# oneDpong.net
KiCad netlist of a schematic drawn in EAGLE
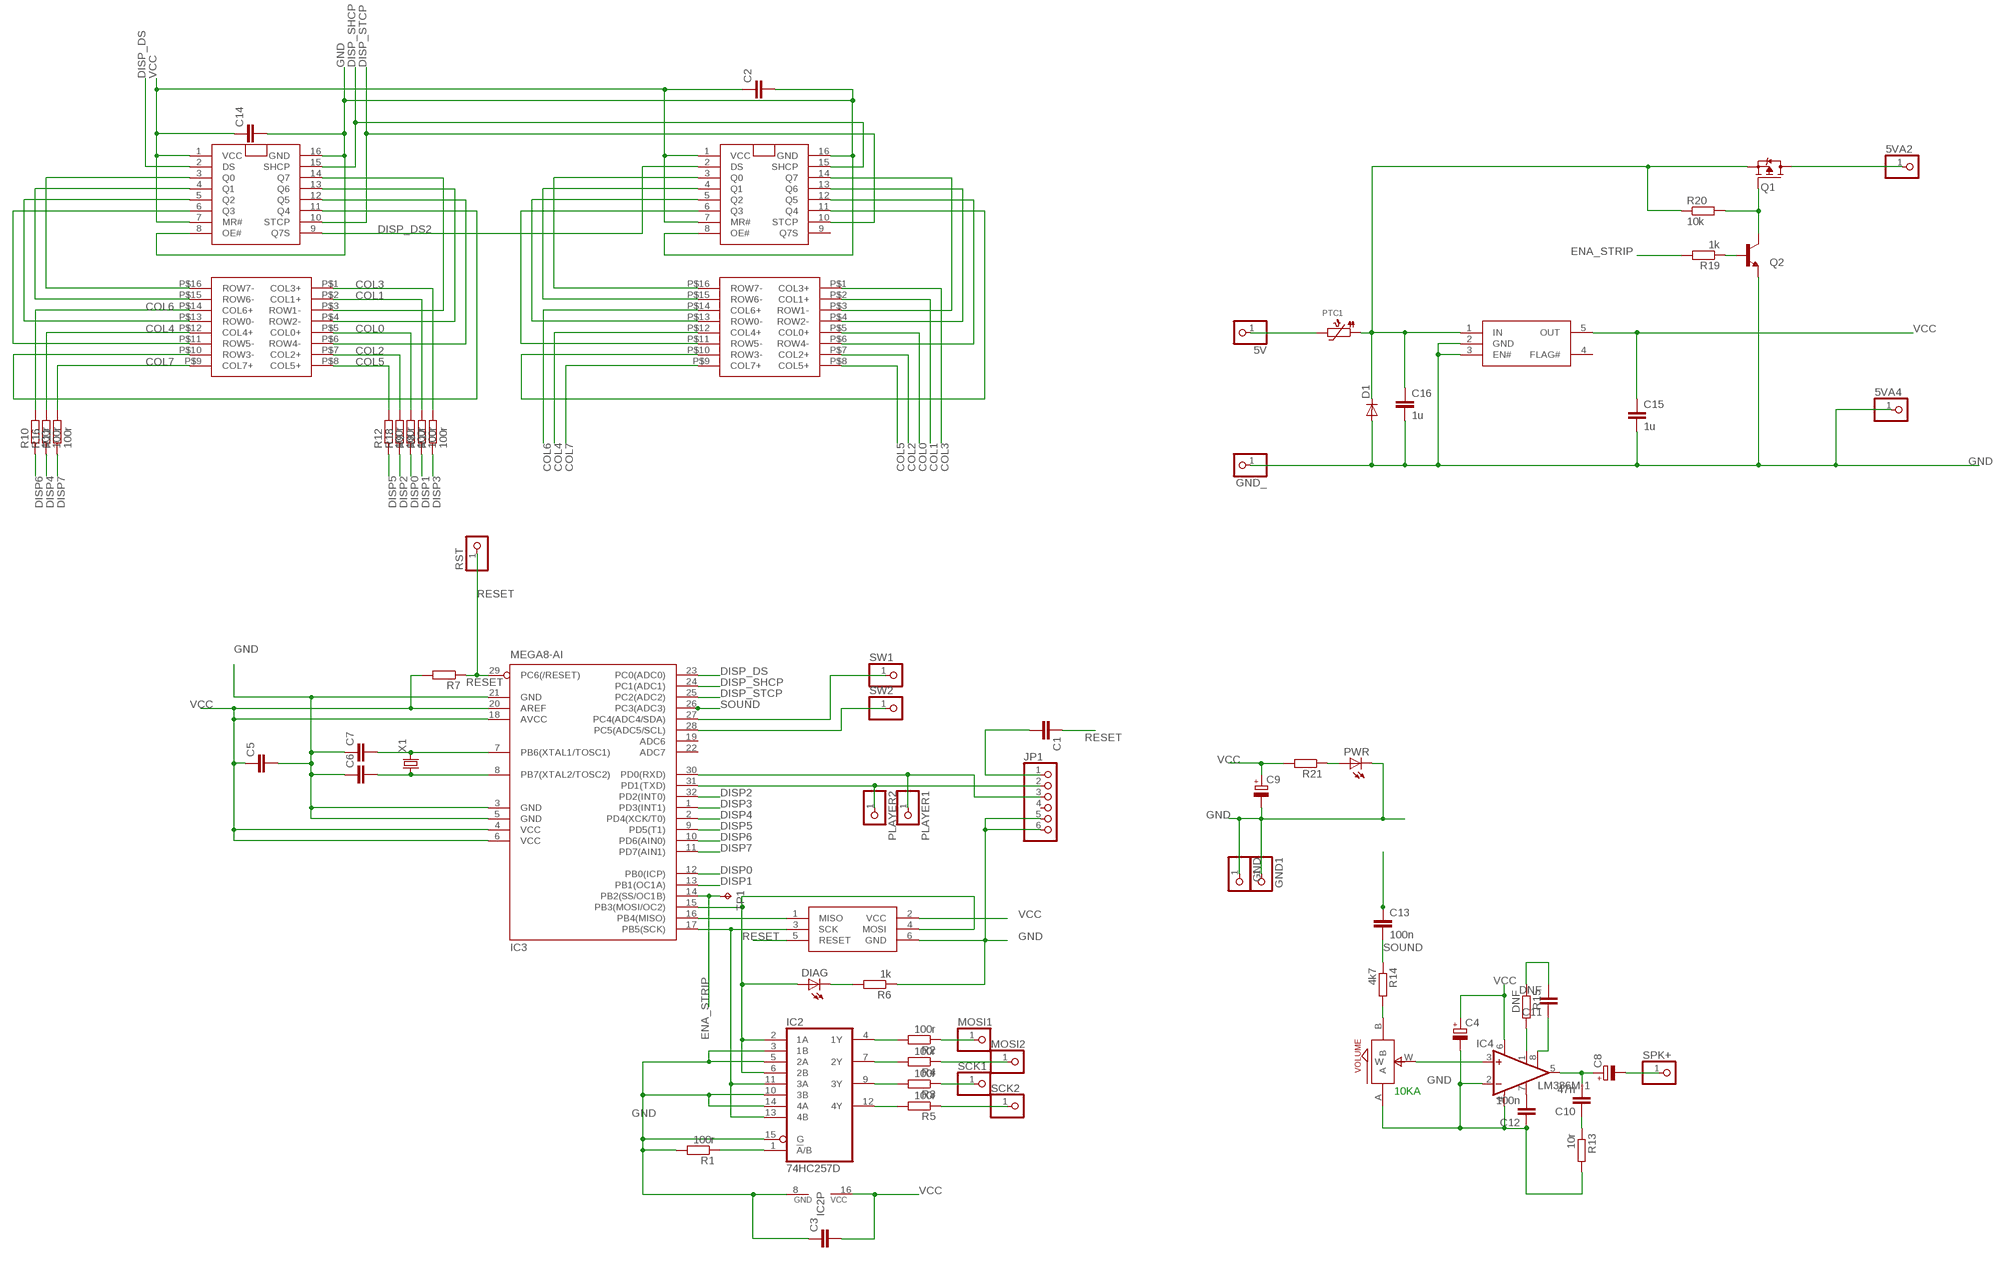
[diagram p0: schematic, sheet 1]

(export (version "E")
  (design (tool "Eeschema 10.0.6"))
  (components
    (comp (ref "5V")
      (value "PINHD-1X1")
      (footprint "eagle-import:1X01")
      (libsource (lib "eagle-import") (part "PINHD-1X1"))
    )
    (comp (ref "5VA2")
      (value "PINHD-1X1")
      (footprint "eagle-import:1X01")
      (libsource (lib "eagle-import") (part "PINHD-1X1"))
    )
    (comp (ref "5VA4")
      (value "PINHD-1X1")
      (footprint "eagle-import:1X01")
      (libsource (lib "eagle-import") (part "PINHD-1X1"))
    )
    (comp (ref "C1")
      (value "C-EUC0805")
      (footprint "eagle-import:C0805")
      (libsource (lib "eagle-import") (part "C-EUC0805"))
    )
    (comp (ref "C2")
      (value "C-EUC0805")
      (footprint "eagle-import:C0805")
      (libsource (lib "eagle-import") (part "C-EUC0805"))
    )
    (comp (ref "C3")
      (value "C-EUC0805")
      (footprint "eagle-import:C0805")
      (libsource (lib "eagle-import") (part "C-EUC0805"))
    )
    (comp (ref "C4")
      (value "CPOL-EUE2.5-6")
      (footprint "eagle-import:E2,5-6")
      (libsource (lib "eagle-import") (part "CPOL-EUE2.5-6"))
    )
    (comp (ref "C5")
      (value "C-EUC0805")
      (footprint "eagle-import:C0805")
      (libsource (lib "eagle-import") (part "C-EUC0805"))
    )
    (comp (ref "C6")
      (value "C-EUC0805")
      (footprint "eagle-import:C0805")
      (libsource (lib "eagle-import") (part "C-EUC0805"))
    )
    (comp (ref "C7")
      (value "C-EUC0805")
      (footprint "eagle-import:C0805")
      (libsource (lib "eagle-import") (part "C-EUC0805"))
    )
    (comp (ref "C8")
      (value "CPOL-EUE2.5-6")
      (footprint "eagle-import:E2,5-6")
      (libsource (lib "eagle-import") (part "CPOL-EUE2.5-6"))
    )
    (comp (ref "C9")
      (value "CPOL-EUE2.5-6")
      (footprint "eagle-import:E2,5-6")
      (libsource (lib "eagle-import") (part "CPOL-EUE2.5-6"))
    )
    (comp (ref "C10")
      (value "47n")
      (footprint "eagle-import:C0805")
      (libsource (lib "eagle-import") (part "C-EUC0805"))
    )
    (comp (ref "C11")
      (value "DNF")
      (footprint "eagle-import:C0805")
      (libsource (lib "eagle-import") (part "C-EUC0805"))
    )
    (comp (ref "C12")
      (value "100n")
      (footprint "eagle-import:C0805")
      (libsource (lib "eagle-import") (part "C-EUC0805"))
    )
    (comp (ref "C13")
      (value "100n")
      (footprint "eagle-import:C0805")
      (libsource (lib "eagle-import") (part "C-EUC0805"))
    )
    (comp (ref "C14")
      (value "C-EUC0805")
      (footprint "eagle-import:C0805")
      (libsource (lib "eagle-import") (part "C-EUC0805"))
    )
    (comp (ref "C15")
      (value "1u")
      (footprint "eagle-import:C0805")
      (libsource (lib "eagle-import") (part "C-EUC0805"))
    )
    (comp (ref "C16")
      (value "1u")
      (footprint "eagle-import:C0805")
      (libsource (lib "eagle-import") (part "C-EUC0805"))
    )
    (comp (ref "D1")
      (value "DIODE-SMC")
      (footprint "eagle-import:SMC")
      (libsource (lib "eagle-import") (part "DIODE-SMC"))
    )
    (comp (ref "DIAG")
      (value "LED3MM")
      (footprint "eagle-import:LED3MM")
      (libsource (lib "eagle-import") (part "LED3MM"))
    )
    (comp (ref "GND")
      (value "PINHD-1X1")
      (footprint "eagle-import:1X01")
      (libsource (lib "eagle-import") (part "PINHD-1X1"))
    )
    (comp (ref "GND1")
      (value "PINHD-1X1")
      (footprint "eagle-import:1X01")
      (libsource (lib "eagle-import") (part "PINHD-1X1"))
    )
    (comp (ref "GND_")
      (value "PINHD-1X1")
      (footprint "eagle-import:1X01")
      (libsource (lib "eagle-import") (part "PINHD-1X1"))
    )
    (comp (ref "IC1")
      (value "NPIC6C596")
      (footprint "eagle-import:SO16")
      (libsource (lib "eagle-import") (part "NPIC6C596"))
    )
    (comp (ref "IC2")
      (value "74HC257D")
      (footprint "eagle-import:SO16")
      (libsource (lib "eagle-import") (part "74257DHC"))
    )
    (comp (ref "IC3")
      (value "MEGA8-AI")
      (footprint "eagle-import:TQFP32-08")
      (fields (field (name "MPN") "ATMEGA8-16AU"))
      (libsource (lib "eagle-import") (part "MEGA8-AI"))
    )
    (comp (ref "IC4")
      (value "LM386M-1")
      (footprint "eagle-import:SO08")
      (libsource (lib "eagle-import") (part "LM386?-M1"))
    )
    (comp (ref "IC5")
      (value "NPIC6C596")
      (footprint "eagle-import:SO16")
      (libsource (lib "eagle-import") (part "NPIC6C596"))
    )
    (comp (ref "IC6")
      (value "NCP361SNT1G")
      (footprint "eagle-import:SOT23-5")
      (libsource (lib "eagle-import") (part "NCP361SNT1G"))
    )
    (comp (ref "ICSP")
      (value "TAG_CONN_AVR")
      (footprint "eagle-import:TC2030-MCP-NL")
      (libsource (lib "eagle-import") (part "TAG_CONN_AVR"))
    )
    (comp (ref "JP1")
      (value "PINHD-1X6")
      (footprint "eagle-import:1X06")
      (libsource (lib "eagle-import") (part "PINHD-1X6"))
    )
    (comp (ref "MOSI1")
      (value "PINHD-1X1")
      (footprint "eagle-import:1X01")
      (libsource (lib "eagle-import") (part "PINHD-1X1"))
    )
    (comp (ref "MOSI2")
      (value "PINHD-1X1")
      (footprint "eagle-import:1X01")
      (libsource (lib "eagle-import") (part "PINHD-1X1"))
    )
    (comp (ref "PLAYER1")
      (value "PINHD-1X1")
      (footprint "eagle-import:1X01")
      (libsource (lib "eagle-import") (part "PINHD-1X1"))
    )
    (comp (ref "PLAYER2")
      (value "PINHD-1X1")
      (footprint "eagle-import:1X01")
      (libsource (lib "eagle-import") (part "PINHD-1X1"))
    )
    (comp (ref "PTC1")
      (value "PTC1812")
      (footprint "eagle-import:PTC1812")
      (libsource (lib "eagle-import") (part "PTC1812"))
    )
    (comp (ref "PWR")
      (value "LED3MM")
      (footprint "eagle-import:LED3MM")
      (libsource (lib "eagle-import") (part "LED3MM"))
    )
    (comp (ref "Q1")
      (value "SPD30P06PTO252")
      (footprint "eagle-import:TO252")
      (libsource (lib "eagle-import") (part "SPD30P06PTO252"))
    )
    (comp (ref "Q2")
      (value "MMBT3904LT1-NPN-SOT23-BEC")
      (footprint "eagle-import:SOT23-BEC")
      (libsource (lib "eagle-import") (part "-NPN-SOT23-BECMMBT3904LT1"))
    )
    (comp (ref "R1")
      (value "100r")
      (footprint "eagle-import:R0805")
      (libsource (lib "eagle-import") (part "R-EU_R0805"))
    )
    (comp (ref "R2")
      (value "100r")
      (footprint "eagle-import:R0805")
      (libsource (lib "eagle-import") (part "R-EU_R0805"))
    )
    (comp (ref "R3")
      (value "100r")
      (footprint "eagle-import:R0805")
      (libsource (lib "eagle-import") (part "R-EU_R0805"))
    )
    (comp (ref "R4")
      (value "100r")
      (footprint "eagle-import:R0805")
      (libsource (lib "eagle-import") (part "R-EU_R0805"))
    )
    (comp (ref "R5")
      (value "100r")
      (footprint "eagle-import:R0805")
      (libsource (lib "eagle-import") (part "R-EU_R0805"))
    )
    (comp (ref "R6")
      (value "1k")
      (footprint "eagle-import:R0805")
      (libsource (lib "eagle-import") (part "R-EU_R0805"))
    )
    (comp (ref "R7")
      (value "R-EU_R0805")
      (footprint "eagle-import:R0805")
      (libsource (lib "eagle-import") (part "R-EU_R0805"))
    )
    (comp (ref "R8")
      (value "100r")
      (footprint "eagle-import:R0805")
      (libsource (lib "eagle-import") (part "R-EU_R0805"))
    )
    (comp (ref "R9")
      (value "100r")
      (footprint "eagle-import:R0805")
      (libsource (lib "eagle-import") (part "R-EU_R0805"))
    )
    (comp (ref "R10")
      (value "100r")
      (footprint "eagle-import:R0805")
      (libsource (lib "eagle-import") (part "R-EU_R0805"))
    )
    (comp (ref "R11")
      (value "100r")
      (footprint "eagle-import:R0805")
      (libsource (lib "eagle-import") (part "R-EU_R0805"))
    )
    (comp (ref "R12")
      (value "100r")
      (footprint "eagle-import:R0805")
      (libsource (lib "eagle-import") (part "R-EU_R0805"))
    )
    (comp (ref "R13")
      (value "10r")
      (footprint "eagle-import:R0805")
      (libsource (lib "eagle-import") (part "R-EU_R0805"))
    )
    (comp (ref "R14")
      (value "4k7")
      (footprint "eagle-import:R0805")
      (libsource (lib "eagle-import") (part "R-EU_R0805"))
    )
    (comp (ref "R15")
      (value "DNF")
      (footprint "eagle-import:R0805")
      (libsource (lib "eagle-import") (part "R-EU_R0805"))
    )
    (comp (ref "R16")
      (value "100r")
      (footprint "eagle-import:R0805")
      (libsource (lib "eagle-import") (part "R-EU_R0805"))
    )
    (comp (ref "R17")
      (value "100r")
      (footprint "eagle-import:R0805")
      (libsource (lib "eagle-import") (part "R-EU_R0805"))
    )
    (comp (ref "R18")
      (value "100r")
      (footprint "eagle-import:R0805")
      (libsource (lib "eagle-import") (part "R-EU_R0805"))
    )
    (comp (ref "R19")
      (value "1k")
      (footprint "eagle-import:R0805")
      (libsource (lib "eagle-import") (part "R-EU_R0805"))
    )
    (comp (ref "R20")
      (value "10k")
      (footprint "eagle-import:R0805")
      (libsource (lib "eagle-import") (part "R-EU_R0805"))
    )
    (comp (ref "R21")
      (value "R-EU_R0805")
      (footprint "eagle-import:R0805")
      (libsource (lib "eagle-import") (part "R-EU_R0805"))
    )
    (comp (ref "RST")
      (value "PINHD-1X1")
      (footprint "eagle-import:1X01")
      (libsource (lib "eagle-import") (part "PINHD-1X1"))
    )
    (comp (ref "SCK1")
      (value "PINHD-1X1")
      (footprint "eagle-import:1X01")
      (libsource (lib "eagle-import") (part "PINHD-1X1"))
    )
    (comp (ref "SCK2")
      (value "PINHD-1X1")
      (footprint "eagle-import:1X01")
      (libsource (lib "eagle-import") (part "PINHD-1X1"))
    )
    (comp (ref "SPK+")
      (value "PINHD-1X1")
      (footprint "eagle-import:1X01")
      (libsource (lib "eagle-import") (part "PINHD-1X1"))
    )
    (comp (ref "SW1")
      (value "PINHD-1X1")
      (footprint "eagle-import:1X01")
      (libsource (lib "eagle-import") (part "PINHD-1X1"))
    )
    (comp (ref "SW2")
      (value "PINHD-1X1")
      (footprint "eagle-import:1X01")
      (libsource (lib "eagle-import") (part "PINHD-1X1"))
    )
    (comp (ref "TP1")
      (value "TPB1,27")
      (footprint "eagle-import:B1,27")
      (libsource (lib "eagle-import") (part "TPB1,27"))
    )
    (comp (ref "U$1")
      (value "LARGE8X8")
      (footprint "eagle-import:LARGE8X8")
      (libsource (lib "eagle-import") (part "LARGE8X8"))
    )
    (comp (ref "U$2")
      (value "LARGE8X8")
      (footprint "eagle-import:LARGE8X8")
      (libsource (lib "eagle-import") (part "LARGE8X8"))
    )
    (comp (ref "VOLUME")
      (value "ALPS_POT_SMALL")
      (footprint "eagle-import:SMALL_ALPS_POT")
      (libsource (lib "eagle-import") (part "ALPS_POT_SMALL"))
    )
    (comp (ref "X1")
      (value "CRYSTALHC49U-V")
      (footprint "eagle-import:HC49U-V")
      (libsource (lib "eagle-import") (part "CRYSTALHC49U-V"))
    )
  )
  (nets
    (net (code "1") (name "/COL0") (class "Default")
      (node (ref "R9") (pin "2") (pinfunction "2_2") (pintype "passive"))
      (node (ref "U$1") (pin "P$5") (pinfunction "COL0+_P$5") (pintype "bidirectional"))
      (node (ref "U$2") (pin "P$5") (pinfunction "COL0+_P$5") (pintype "bidirectional"))
    )
    (net (code "2") (name "/COL1") (class "Default")
      (node (ref "R8") (pin "2") (pinfunction "2_2") (pintype "passive"))
      (node (ref "U$1") (pin "P$2") (pinfunction "COL1+_P$2") (pintype "bidirectional"))
      (node (ref "U$2") (pin "P$2") (pinfunction "COL1+_P$2") (pintype "bidirectional"))
    )
    (net (code "3") (name "/COL2") (class "Default")
      (node (ref "R18") (pin "2") (pinfunction "2_2") (pintype "passive"))
      (node (ref "U$1") (pin "P$7") (pinfunction "COL2+_P$7") (pintype "bidirectional"))
      (node (ref "U$2") (pin "P$7") (pinfunction "COL2+_P$7") (pintype "bidirectional"))
    )
    (net (code "4") (name "/COL3") (class "Default")
      (node (ref "R17") (pin "2") (pinfunction "2_2") (pintype "passive"))
      (node (ref "U$1") (pin "P$1") (pinfunction "COL3+_P$1") (pintype "bidirectional"))
      (node (ref "U$2") (pin "P$1") (pinfunction "COL3+_P$1") (pintype "bidirectional"))
    )
    (net (code "5") (name "/COL4") (class "Default")
      (node (ref "R16") (pin "2") (pinfunction "2_2") (pintype "passive"))
      (node (ref "U$1") (pin "P$12") (pinfunction "COL4+_P$12") (pintype "bidirectional"))
      (node (ref "U$2") (pin "P$12") (pinfunction "COL4+_P$12") (pintype "bidirectional"))
    )
    (net (code "6") (name "/COL5") (class "Default")
      (node (ref "R12") (pin "2") (pinfunction "2_2") (pintype "passive"))
      (node (ref "U$1") (pin "P$8") (pinfunction "COL5+_P$8") (pintype "bidirectional"))
      (node (ref "U$2") (pin "P$8") (pinfunction "COL5+_P$8") (pintype "bidirectional"))
    )
    (net (code "7") (name "/COL6") (class "Default")
      (node (ref "R10") (pin "2") (pinfunction "2_2") (pintype "passive"))
      (node (ref "U$1") (pin "P$14") (pinfunction "COL6+_P$14") (pintype "bidirectional"))
      (node (ref "U$2") (pin "P$14") (pinfunction "COL6+_P$14") (pintype "bidirectional"))
    )
    (net (code "8") (name "/COL7") (class "Default")
      (node (ref "R11") (pin "2") (pinfunction "2_2") (pintype "passive"))
      (node (ref "U$1") (pin "P$9") (pinfunction "COL7+_P$9") (pintype "bidirectional"))
      (node (ref "U$2") (pin "P$9") (pinfunction "COL7+_P$9") (pintype "bidirectional"))
    )
    (net (code "9") (name "/DISP0") (class "Default")
      (node (ref "IC3") (pin "12") (pinfunction "PB0(ICP)_12") (pintype "bidirectional"))
      (node (ref "R9") (pin "1") (pinfunction "1_1") (pintype "passive"))
    )
    (net (code "10") (name "/DISP1") (class "Default")
      (node (ref "IC3") (pin "13") (pinfunction "PB1(OC1A)_13") (pintype "bidirectional"))
      (node (ref "R8") (pin "1") (pinfunction "1_1") (pintype "passive"))
    )
    (net (code "11") (name "/DISP2") (class "Default")
      (node (ref "IC3") (pin "32") (pinfunction "PD2(INT0)_32") (pintype "bidirectional"))
      (node (ref "R18") (pin "1") (pinfunction "1_1") (pintype "passive"))
    )
    (net (code "12") (name "/DISP3") (class "Default")
      (node (ref "IC3") (pin "1") (pinfunction "PD3(INT1)_1") (pintype "bidirectional"))
      (node (ref "R17") (pin "1") (pinfunction "1_1") (pintype "passive"))
    )
    (net (code "13") (name "/DISP4") (class "Default")
      (node (ref "IC3") (pin "2") (pinfunction "PD4(XCK/T0)_2") (pintype "bidirectional"))
      (node (ref "R16") (pin "1") (pinfunction "1_1") (pintype "passive"))
    )
    (net (code "14") (name "/DISP5") (class "Default")
      (node (ref "IC3") (pin "9") (pinfunction "PD5(T1)_9") (pintype "bidirectional"))
      (node (ref "R12") (pin "1") (pinfunction "1_1") (pintype "passive"))
    )
    (net (code "15") (name "/DISP6") (class "Default")
      (node (ref "IC3") (pin "10") (pinfunction "PD6(AIN0)_10") (pintype "bidirectional"))
      (node (ref "R10") (pin "1") (pinfunction "1_1") (pintype "passive"))
    )
    (net (code "16") (name "/DISP7") (class "Default")
      (node (ref "IC3") (pin "11") (pinfunction "PD7(AIN1)_11") (pintype "bidirectional"))
      (node (ref "R11") (pin "1") (pinfunction "1_1") (pintype "passive"))
    )
    (net (code "17") (name "/DISP_DS") (class "Default")
      (node (ref "IC3") (pin "23") (pinfunction "PC0(ADC0)_23") (pintype "bidirectional"))
      (node (ref "IC5") (pin "2") (pinfunction "DS_2") (pintype "input"))
    )
    (net (code "18") (name "/DISP_DS2") (class "Default")
      (node (ref "IC1") (pin "2") (pinfunction "DS_2") (pintype "input"))
      (node (ref "IC5") (pin "9") (pinfunction "Q7S_9") (pintype "output"))
    )
    (net (code "19") (name "/DISP_SHCP") (class "Default")
      (node (ref "IC1") (pin "15") (pinfunction "SHCP_15") (pintype "input"))
      (node (ref "IC3") (pin "24") (pinfunction "PC1(ADC1)_24") (pintype "bidirectional"))
      (node (ref "IC5") (pin "15") (pinfunction "SHCP_15") (pintype "input"))
    )
    (net (code "20") (name "/DISP_STCP") (class "Default")
      (node (ref "IC1") (pin "10") (pinfunction "STCP_10") (pintype "input"))
      (node (ref "IC3") (pin "25") (pinfunction "PC2(ADC2)_25") (pintype "bidirectional"))
      (node (ref "IC5") (pin "10") (pinfunction "STCP_10") (pintype "input"))
    )
    (net (code "21") (name "/ENA_STRIP") (class "Default")
      (node (ref "IC3") (pin "14") (pinfunction "PB2(SS/OC1B)_14") (pintype "bidirectional"))
      (node (ref "R19") (pin "2") (pinfunction "2_2") (pintype "passive"))
      (node (ref "TP1") (pin "TP") (pinfunction "TP_TP") (pintype "input"))
    )
    (net (code "22") (name "/GND") (class "Default")
      (node (ref "5VA4") (pin "1") (pinfunction "1_1") (pintype "passive"))
      (node (ref "C12") (pin "1") (pinfunction "1_1") (pintype "passive"))
      (node (ref "C14") (pin "2") (pinfunction "2_2") (pintype "passive"))
      (node (ref "C15") (pin "2") (pinfunction "2_2") (pintype "passive"))
      (node (ref "C16") (pin "2") (pinfunction "2_2") (pintype "passive"))
      (node (ref "C2") (pin "2") (pinfunction "2_2") (pintype "passive"))
      (node (ref "C3") (pin "1") (pinfunction "1_1") (pintype "passive"))
      (node (ref "C4") (pin "-") (pinfunction "-_-") (pintype "passive"))
      (node (ref "C5") (pin "2") (pinfunction "2_2") (pintype "passive"))
      (node (ref "C6") (pin "1") (pinfunction "1_1") (pintype "passive"))
      (node (ref "C7") (pin "1") (pinfunction "1_1") (pintype "passive"))
      (node (ref "C9") (pin "-") (pinfunction "-_-") (pintype "passive"))
      (node (ref "D1") (pin "A") (pinfunction "A_A") (pintype "passive"))
      (node (ref "GND") (pin "1") (pinfunction "1_1") (pintype "passive"))
      (node (ref "GND1") (pin "1") (pinfunction "1_1") (pintype "passive"))
      (node (ref "GND_") (pin "1") (pinfunction "1_1") (pintype "passive"))
      (node (ref "IC1") (pin "16") (pinfunction "GND_16") (pintype "power_in"))
      (node (ref "IC1") (pin "8") (pinfunction "OE#_8") (pintype "input"))
      (node (ref "IC2") (pin "10") (pinfunction "3B_10") (pintype "input"))
      (node (ref "IC2") (pin "14") (pinfunction "4A_14") (pintype "input"))
      (node (ref "IC2") (pin "15") (pinfunction "G_15") (pintype "input"))
      (node (ref "IC2") (pin "3") (pinfunction "1B_3") (pintype "input"))
      (node (ref "IC2") (pin "5") (pinfunction "2A_5") (pintype "input"))
      (node (ref "IC2") (pin "8") (pinfunction "GND_8") (pintype "power_in"))
      (node (ref "IC3") (pin "21") (pinfunction "GND_21") (pintype "power_in"))
      (node (ref "IC3") (pin "3") (pinfunction "GND_3") (pintype "power_in"))
      (node (ref "IC3") (pin "5") (pinfunction "GND_5") (pintype "power_in"))
      (node (ref "IC4") (pin "2") (pinfunction "-IN_2") (pintype "input"))
      (node (ref "IC4") (pin "4") (pinfunction "GND_4") (pintype "power_in"))
      (node (ref "IC5") (pin "16") (pinfunction "GND_16") (pintype "power_in"))
      (node (ref "IC5") (pin "8") (pinfunction "OE#_8") (pintype "input"))
      (node (ref "IC6") (pin "2") (pinfunction "GND_2") (pintype "bidirectional"))
      (node (ref "IC6") (pin "3") (pinfunction "EN#_3") (pintype "bidirectional"))
      (node (ref "ICSP") (pin "6") (pinfunction "GND_6") (pintype "power_in"))
      (node (ref "JP1") (pin "5") (pinfunction "5_5") (pintype "passive"))
      (node (ref "JP1") (pin "6") (pinfunction "6_6") (pintype "passive"))
      (node (ref "PWR") (pin "K") (pinfunction "C_K") (pintype "passive"))
      (node (ref "Q2") (pin "E") (pinfunction "E_E") (pintype "passive"))
      (node (ref "R1") (pin "2") (pinfunction "2_2") (pintype "passive"))
      (node (ref "R13") (pin "2") (pinfunction "2_2") (pintype "passive"))
      (node (ref "R6") (pin "1") (pinfunction "1_1") (pintype "passive"))
      (node (ref "VOLUME") (pin "A") (pinfunction "A_A") (pintype "bidirectional"))
    )
    (net (code "23") (name "/RESET") (class "Default")
      (node (ref "C1") (pin "1") (pinfunction "1_1") (pintype "passive"))
      (node (ref "IC3") (pin "29") (pinfunction "PC6(/RESET)_29") (pintype "bidirectional"))
      (node (ref "ICSP") (pin "5") (pinfunction "RESET_5") (pintype "bidirectional"))
      (node (ref "R7") (pin "1") (pinfunction "1_1") (pintype "passive"))
      (node (ref "RST") (pin "1") (pinfunction "1_1") (pintype "passive"))
    )
    (net (code "24") (name "/SOUND") (class "Default")
      (node (ref "C13") (pin "1") (pinfunction "1_1") (pintype "passive"))
      (node (ref "IC3") (pin "26") (pinfunction "PC3(ADC3)_26") (pintype "bidirectional"))
    )
    (net (code "25") (name "/VCC") (class "Default")
      (node (ref "C14") (pin "1") (pinfunction "1_1") (pintype "passive"))
      (node (ref "C15") (pin "1") (pinfunction "1_1") (pintype "passive"))
      (node (ref "C2") (pin "1") (pinfunction "1_1") (pintype "passive"))
      (node (ref "C3") (pin "2") (pinfunction "2_2") (pintype "passive"))
      (node (ref "C4") (pin "+") (pinfunction "+_+") (pintype "passive"))
      (node (ref "C5") (pin "1") (pinfunction "1_1") (pintype "passive"))
      (node (ref "C9") (pin "+") (pinfunction "+_+") (pintype "passive"))
      (node (ref "IC1") (pin "1") (pinfunction "VCC_1") (pintype "power_in"))
      (node (ref "IC1") (pin "7") (pinfunction "MR#_7") (pintype "input"))
      (node (ref "IC2") (pin "16") (pinfunction "VCC_16") (pintype "power_in"))
      (node (ref "IC3") (pin "18") (pinfunction "AVCC_18") (pintype "power_in"))
      (node (ref "IC3") (pin "20") (pinfunction "AREF_20") (pintype "passive"))
      (node (ref "IC3") (pin "4") (pinfunction "VCC_4") (pintype "power_in"))
      (node (ref "IC3") (pin "6") (pinfunction "VCC_6") (pintype "power_in"))
      (node (ref "IC4") (pin "6") (pinfunction "VS_6") (pintype "power_in"))
      (node (ref "IC5") (pin "1") (pinfunction "VCC_1") (pintype "power_in"))
      (node (ref "IC5") (pin "7") (pinfunction "MR#_7") (pintype "input"))
      (node (ref "IC6") (pin "5") (pinfunction "OUT_5") (pintype "bidirectional"))
      (node (ref "ICSP") (pin "2") (pinfunction "VCC_2") (pintype "power_in"))
      (node (ref "R21") (pin "2") (pinfunction "2_2") (pintype "passive"))
      (node (ref "R7") (pin "2") (pinfunction "2_2") (pintype "passive"))
    )
    (net (code "26") (name "Net-(C1-Pad2)") (class "Default")
      (node (ref "C1") (pin "2") (pinfunction "2_2") (pintype "passive"))
      (node (ref "JP1") (pin "1") (pinfunction "1_1") (pintype "passive"))
    )
    (net (code "27") (name "Net-(C8-Pad-)") (class "Default")
      (node (ref "C8") (pin "-") (pinfunction "-_-") (pintype "passive"))
      (node (ref "SPK+") (pin "1") (pinfunction "1_1") (pintype "passive"))
    )
    (net (code "28") (name "Net-(C10-Pad1)") (class "Default")
      (node (ref "C10") (pin "1") (pinfunction "1_1") (pintype "passive"))
      (node (ref "R13") (pin "1") (pinfunction "1_1") (pintype "passive"))
    )
    (net (code "29") (name "Net-(C11-Pad1)") (class "Default")
      (node (ref "C11") (pin "1") (pinfunction "1_1") (pintype "passive"))
      (node (ref "IC4") (pin "8") (pinfunction "GAIN_8") (pintype "passive"))
    )
    (net (code "30") (name "Net-(C11-Pad2)") (class "Default")
      (node (ref "C11") (pin "2") (pinfunction "2_2") (pintype "passive"))
      (node (ref "R15") (pin "1") (pinfunction "1_1") (pintype "passive"))
    )
    (net (code "31") (name "Net-(C13-Pad2)") (class "Default")
      (node (ref "C13") (pin "2") (pinfunction "2_2") (pintype "passive"))
      (node (ref "R14") (pin "1") (pinfunction "1_1") (pintype "passive"))
    )
    (net (code "32") (name "Net-(DIAG-C)") (class "Default")
      (node (ref "DIAG") (pin "K") (pinfunction "C_K") (pintype "passive"))
      (node (ref "R6") (pin "2") (pinfunction "2_2") (pintype "passive"))
    )
    (net (code "33") (name "Net-(IC1-Q0)") (class "Default")
      (node (ref "IC1") (pin "3") (pinfunction "Q0_3") (pintype "open_collector"))
      (node (ref "U$2") (pin "P$16") (pinfunction "ROW7-_P$16") (pintype "bidirectional"))
    )
    (net (code "34") (name "Net-(IC1-Q1)") (class "Default")
      (node (ref "IC1") (pin "4") (pinfunction "Q1_4") (pintype "open_collector"))
      (node (ref "U$2") (pin "P$15") (pinfunction "ROW6-_P$15") (pintype "bidirectional"))
    )
    (net (code "35") (name "Net-(IC1-Q2)") (class "Default")
      (node (ref "IC1") (pin "5") (pinfunction "Q2_5") (pintype "open_collector"))
      (node (ref "U$2") (pin "P$13") (pinfunction "ROW0-_P$13") (pintype "bidirectional"))
    )
    (net (code "36") (name "Net-(IC1-Q3)") (class "Default")
      (node (ref "IC1") (pin "6") (pinfunction "Q3_6") (pintype "open_collector"))
      (node (ref "U$2") (pin "P$11") (pinfunction "ROW5-_P$11") (pintype "bidirectional"))
    )
    (net (code "37") (name "Net-(IC1-Q4)") (class "Default")
      (node (ref "IC1") (pin "11") (pinfunction "Q4_11") (pintype "open_collector"))
      (node (ref "U$2") (pin "P$10") (pinfunction "ROW3-_P$10") (pintype "bidirectional"))
    )
    (net (code "38") (name "Net-(IC1-Q5)") (class "Default")
      (node (ref "IC1") (pin "12") (pinfunction "Q5_12") (pintype "open_collector"))
      (node (ref "U$2") (pin "P$6") (pinfunction "ROW4-_P$6") (pintype "bidirectional"))
    )
    (net (code "39") (name "Net-(IC1-Q6)") (class "Default")
      (node (ref "IC1") (pin "13") (pinfunction "Q6_13") (pintype "open_collector"))
      (node (ref "U$2") (pin "P$4") (pinfunction "ROW2-_P$4") (pintype "bidirectional"))
    )
    (net (code "40") (name "Net-(IC1-Q7)") (class "Default")
      (node (ref "IC1") (pin "14") (pinfunction "Q7_14") (pintype "open_collector"))
      (node (ref "U$2") (pin "P$3") (pinfunction "ROW1-_P$3") (pintype "bidirectional"))
    )
    (net (code "41") (name "Net-(IC2A-1A)") (class "Default")
      (node (ref "DIAG") (pin "A") (pinfunction "A_A") (pintype "passive"))
      (node (ref "IC2") (pin "2") (pinfunction "1A_2") (pintype "input"))
      (node (ref "IC2") (pin "6") (pinfunction "2B_6") (pintype "input"))
      (node (ref "IC3") (pin "15") (pinfunction "PB3(MOSI/OC2)_15") (pintype "bidirectional"))
      (node (ref "ICSP") (pin "4") (pinfunction "MOSI_4") (pintype "bidirectional"))
    )
    (net (code "42") (name "Net-(IC2A-1Y)") (class "Default")
      (node (ref "IC2") (pin "4") (pinfunction "1Y_4") (pintype "tri_state"))
      (node (ref "R2") (pin "2") (pinfunction "2_2") (pintype "passive"))
    )
    (net (code "43") (name "Net-(IC2A-2Y)") (class "Default")
      (node (ref "IC2") (pin "7") (pinfunction "2Y_7") (pintype "tri_state"))
      (node (ref "R4") (pin "2") (pinfunction "2_2") (pintype "passive"))
    )
    (net (code "44") (name "Net-(IC2A-3A)") (class "Default")
      (node (ref "IC2") (pin "11") (pinfunction "3A_11") (pintype "input"))
      (node (ref "IC2") (pin "13") (pinfunction "4B_13") (pintype "input"))
      (node (ref "IC3") (pin "17") (pinfunction "PB5(SCK)_17") (pintype "bidirectional"))
      (node (ref "ICSP") (pin "3") (pinfunction "SCK_3") (pintype "bidirectional"))
    )
    (net (code "45") (name "Net-(IC2A-3Y)") (class "Default")
      (node (ref "IC2") (pin "9") (pinfunction "3Y_9") (pintype "tri_state"))
      (node (ref "R3") (pin "2") (pinfunction "2_2") (pintype "passive"))
    )
    (net (code "46") (name "Net-(IC2A-4Y)") (class "Default")
      (node (ref "IC2") (pin "12") (pinfunction "4Y_12") (pintype "tri_state"))
      (node (ref "R5") (pin "2") (pinfunction "2_2") (pintype "passive"))
    )
    (net (code "47") (name "Net-(IC2A-~{A}{slash}B)") (class "Default")
      (node (ref "IC2") (pin "1") (pinfunction "~{A}/B_1") (pintype "input"))
      (node (ref "R1") (pin "1") (pinfunction "1_1") (pintype "passive"))
    )
    (net (code "48") (name "Net-(IC3-PB4(MISO))") (class "Default")
      (node (ref "IC3") (pin "16") (pinfunction "PB4(MISO)_16") (pintype "bidirectional"))
      (node (ref "ICSP") (pin "1") (pinfunction "MISO_1") (pintype "bidirectional"))
    )
    (net (code "49") (name "Net-(IC3-PB6(XTAL1{slash}TOSC1))") (class "Default")
      (node (ref "C7") (pin "2") (pinfunction "2_2") (pintype "passive"))
      (node (ref "IC3") (pin "7") (pinfunction "PB6(XTAL1/TOSC1)_7") (pintype "bidirectional"))
      (node (ref "X1") (pin "2") (pinfunction "2_2") (pintype "passive"))
    )
    (net (code "50") (name "Net-(IC3-PB7(XTAL2{slash}TOSC2))") (class "Default")
      (node (ref "C6") (pin "2") (pinfunction "2_2") (pintype "passive"))
      (node (ref "IC3") (pin "8") (pinfunction "PB7(XTAL2/TOSC2)_8") (pintype "bidirectional"))
      (node (ref "X1") (pin "1") (pinfunction "1_1") (pintype "passive"))
    )
    (net (code "51") (name "Net-(IC3-PC4(ADC4{slash}SDA))") (class "Default")
      (node (ref "IC3") (pin "27") (pinfunction "PC4(ADC4/SDA)_27") (pintype "bidirectional"))
      (node (ref "SW1") (pin "1") (pinfunction "1_1") (pintype "passive"))
    )
    (net (code "52") (name "Net-(IC3-PC5(ADC5{slash}SCL))") (class "Default")
      (node (ref "IC3") (pin "28") (pinfunction "PC5(ADC5/SCL)_28") (pintype "bidirectional"))
      (node (ref "SW2") (pin "1") (pinfunction "1_1") (pintype "passive"))
    )
    (net (code "53") (name "Net-(IC3-PD0(RXD))") (class "Default")
      (node (ref "IC3") (pin "30") (pinfunction "PD0(RXD)_30") (pintype "bidirectional"))
      (node (ref "JP1") (pin "3") (pinfunction "3_3") (pintype "passive"))
      (node (ref "PLAYER1") (pin "1") (pinfunction "1_1") (pintype "passive"))
    )
    (net (code "54") (name "Net-(IC3-PD1(TXD))") (class "Default")
      (node (ref "IC3") (pin "31") (pinfunction "PD1(TXD)_31") (pintype "bidirectional"))
      (node (ref "JP1") (pin "2") (pinfunction "2_2") (pintype "passive"))
      (node (ref "PLAYER2") (pin "1") (pinfunction "1_1") (pintype "passive"))
    )
    (net (code "55") (name "Net-(IC4-+IN)") (class "Default")
      (node (ref "IC4") (pin "3") (pinfunction "+IN_3") (pintype "input"))
      (node (ref "VOLUME") (pin "W") (pinfunction "W_W") (pintype "bidirectional"))
    )
    (net (code "56") (name "Net-(IC4-BYPASS)") (class "Default")
      (node (ref "C12") (pin "2") (pinfunction "2_2") (pintype "passive"))
      (node (ref "IC4") (pin "7") (pinfunction "BYPASS_7") (pintype "passive"))
    )
    (net (code "57") (name "Net-(IC4-GAIN-Pad1)") (class "Default")
      (node (ref "IC4") (pin "1") (pinfunction "GAIN_1") (pintype "passive"))
      (node (ref "R15") (pin "2") (pinfunction "2_2") (pintype "passive"))
    )
    (net (code "58") (name "Net-(IC4-OUT)") (class "Default")
      (node (ref "C10") (pin "2") (pinfunction "2_2") (pintype "passive"))
      (node (ref "C8") (pin "+") (pinfunction "+_+") (pintype "passive"))
      (node (ref "IC4") (pin "5") (pinfunction "OUT_5") (pintype "output"))
    )
    (net (code "59") (name "Net-(IC5-Q0)") (class "Default")
      (node (ref "IC5") (pin "3") (pinfunction "Q0_3") (pintype "open_collector"))
      (node (ref "U$1") (pin "P$16") (pinfunction "ROW7-_P$16") (pintype "bidirectional"))
    )
    (net (code "60") (name "Net-(IC5-Q1)") (class "Default")
      (node (ref "IC5") (pin "4") (pinfunction "Q1_4") (pintype "open_collector"))
      (node (ref "U$1") (pin "P$15") (pinfunction "ROW6-_P$15") (pintype "bidirectional"))
    )
    (net (code "61") (name "Net-(IC5-Q2)") (class "Default")
      (node (ref "IC5") (pin "5") (pinfunction "Q2_5") (pintype "open_collector"))
      (node (ref "U$1") (pin "P$13") (pinfunction "ROW0-_P$13") (pintype "bidirectional"))
    )
    (net (code "62") (name "Net-(IC5-Q3)") (class "Default")
      (node (ref "IC5") (pin "6") (pinfunction "Q3_6") (pintype "open_collector"))
      (node (ref "U$1") (pin "P$11") (pinfunction "ROW5-_P$11") (pintype "bidirectional"))
    )
    (net (code "63") (name "Net-(IC5-Q4)") (class "Default")
      (node (ref "IC5") (pin "11") (pinfunction "Q4_11") (pintype "open_collector"))
      (node (ref "U$1") (pin "P$10") (pinfunction "ROW3-_P$10") (pintype "bidirectional"))
    )
    (net (code "64") (name "Net-(IC5-Q5)") (class "Default")
      (node (ref "IC5") (pin "12") (pinfunction "Q5_12") (pintype "open_collector"))
      (node (ref "U$1") (pin "P$6") (pinfunction "ROW4-_P$6") (pintype "bidirectional"))
    )
    (net (code "65") (name "Net-(IC5-Q6)") (class "Default")
      (node (ref "IC5") (pin "13") (pinfunction "Q6_13") (pintype "open_collector"))
      (node (ref "U$1") (pin "P$4") (pinfunction "ROW2-_P$4") (pintype "bidirectional"))
    )
    (net (code "66") (name "Net-(IC5-Q7)") (class "Default")
      (node (ref "IC5") (pin "14") (pinfunction "Q7_14") (pintype "open_collector"))
      (node (ref "U$1") (pin "P$3") (pinfunction "ROW1-_P$3") (pintype "bidirectional"))
    )
    (net (code "67") (name "Net-(IC6-IN)") (class "Default")
      (node (ref "C16") (pin "1") (pinfunction "1_1") (pintype "passive"))
      (node (ref "D1") (pin "C") (pinfunction "C_C") (pintype "passive"))
      (node (ref "IC6") (pin "1") (pinfunction "IN_1") (pintype "bidirectional"))
      (node (ref "PTC1") (pin "P$1") (pinfunction "1_P$1") (pintype "passive"))
      (node (ref "Q1") (pin "2") (pinfunction "S_2") (pintype "passive"))
      (node (ref "R20") (pin "1") (pinfunction "1_1") (pintype "passive"))
    )
    (net (code "68") (name "Net-(MOSI1-Pad1)") (class "Default")
      (node (ref "MOSI1") (pin "1") (pinfunction "1_1") (pintype "passive"))
      (node (ref "R2") (pin "1") (pinfunction "1_1") (pintype "passive"))
    )
    (net (code "69") (name "Net-(MOSI2-Pad1)") (class "Default")
      (node (ref "MOSI2") (pin "1") (pinfunction "1_1") (pintype "passive"))
      (node (ref "R4") (pin "1") (pinfunction "1_1") (pintype "passive"))
    )
    (net (code "70") (name "Net-(PTC1-2)") (class "Default")
      (node (ref "5V") (pin "1") (pinfunction "1_1") (pintype "passive"))
      (node (ref "PTC1") (pin "P$2") (pinfunction "2_P$2") (pintype "passive"))
    )
    (net (code "71") (name "Net-(PWR-PadA)") (class "Default")
      (node (ref "PWR") (pin "A") (pinfunction "A_A") (pintype "passive"))
      (node (ref "R21") (pin "1") (pinfunction "1_1") (pintype "passive"))
    )
    (net (code "72") (name "Net-(Q1-D)") (class "Default")
      (node (ref "5VA2") (pin "1") (pinfunction "1_1") (pintype "passive"))
      (node (ref "Q1") (pin "3") (pinfunction "D_3") (pintype "passive"))
    )
    (net (code "73") (name "Net-(Q1-G)") (class "Default")
      (node (ref "Q1") (pin "1") (pinfunction "G_1") (pintype "passive"))
      (node (ref "Q2") (pin "C") (pinfunction "C_C") (pintype "passive"))
      (node (ref "R20") (pin "2") (pinfunction "2_2") (pintype "passive"))
    )
    (net (code "74") (name "Net-(Q2-PadB)") (class "Default")
      (node (ref "Q2") (pin "B") (pinfunction "B_B") (pintype "passive"))
      (node (ref "R19") (pin "1") (pinfunction "1_1") (pintype "passive"))
    )
    (net (code "75") (name "Net-(R3-Pad1)") (class "Default")
      (node (ref "R3") (pin "1") (pinfunction "1_1") (pintype "passive"))
      (node (ref "SCK1") (pin "1") (pinfunction "1_1") (pintype "passive"))
    )
    (net (code "76") (name "Net-(R5-Pad1)") (class "Default")
      (node (ref "R5") (pin "1") (pinfunction "1_1") (pintype "passive"))
      (node (ref "SCK2") (pin "1") (pinfunction "1_1") (pintype "passive"))
    )
    (net (code "77") (name "Net-(R14-Pad2)") (class "Default")
      (node (ref "R14") (pin "2") (pinfunction "2_2") (pintype "passive"))
      (node (ref "VOLUME") (pin "B") (pinfunction "B_B") (pintype "bidirectional"))
    )
    (net (code "78") (name "unconnected-(IC1-Q7S-Pad9)") (class "Default")
      (node (ref "IC1") (pin "9") (pinfunction "Q7S_9") (pintype "output"))
    )
    (net (code "79") (name "unconnected-(IC3-ADC6-Pad19)") (class "Default")
      (node (ref "IC3") (pin "19") (pinfunction "ADC6_19") (pintype "bidirectional"))
    )
    (net (code "80") (name "unconnected-(IC3-ADC7-Pad22)") (class "Default")
      (node (ref "IC3") (pin "22") (pinfunction "ADC7_22") (pintype "bidirectional"))
    )
    (net (code "81") (name "unconnected-(IC6-FLAG#-Pad4)") (class "Default")
      (node (ref "IC6") (pin "4") (pinfunction "FLAG#_4") (pintype "bidirectional"))
    )
    (net (code "82") (name "unconnected-(JP1-Pad4)") (class "Default")
      (node (ref "JP1") (pin "4") (pinfunction "4_4") (pintype "passive"))
    )
  )
)
